# picjug.net
KiCad netlist of a schematic drawn in EAGLE
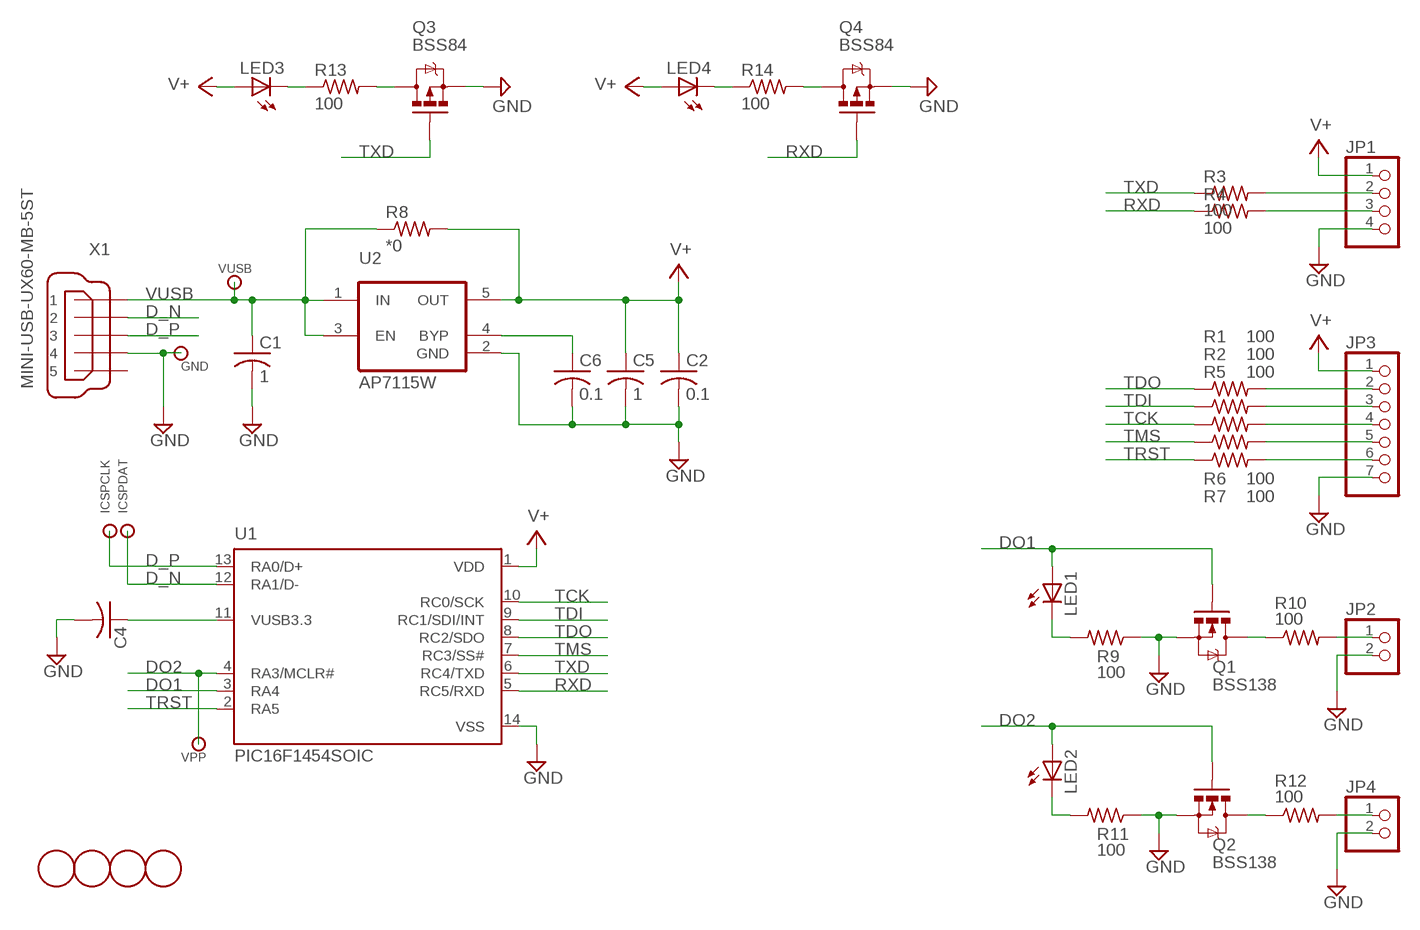
[diagram p0: schematic, sheet 1]

(export (version "E")
  (design (tool "Eeschema 10.0.6"))
  (components
    (comp (ref "C1")
      (value "1")
      (footprint "eagle-import:C0805")
      (libsource (lib "eagle-import") (part "C-USC0805"))
    )
    (comp (ref "C2")
      (value "0.1")
      (footprint "eagle-import:C0805")
      (libsource (lib "eagle-import") (part "C-USC0805"))
    )
    (comp (ref "C4")
      (value "C-USC0805")
      (footprint "eagle-import:C0805")
      (libsource (lib "eagle-import") (part "C-USC0805"))
    )
    (comp (ref "C5")
      (value "1")
      (footprint "eagle-import:C0805")
      (libsource (lib "eagle-import") (part "C-USC0805"))
    )
    (comp (ref "C6")
      (value "0.1")
      (footprint "eagle-import:C0805")
      (libsource (lib "eagle-import") (part "C-USC0805"))
    )
    (comp (ref "GND")
      (value "TESTPOINTMILLMAX_0900_SMALL")
      (footprint "eagle-import:0900-SERIES-SM")
      (libsource (lib "eagle-import") (part "TESTPOINTMILLMAX_0900_SMALL"))
    )
    (comp (ref "ICSPCLK")
      (value "TESTPOINTMILLMAX_0900_SMALL")
      (footprint "eagle-import:0900-SERIES-SM")
      (libsource (lib "eagle-import") (part "TESTPOINTMILLMAX_0900_SMALL"))
    )
    (comp (ref "ICSPDAT")
      (value "TESTPOINTMILLMAX_0900_SMALL")
      (footprint "eagle-import:0900-SERIES-SM")
      (libsource (lib "eagle-import") (part "TESTPOINTMILLMAX_0900_SMALL"))
    )
    (comp (ref "JP1")
      (value "PINHD-1X4")
      (footprint "eagle-import:1X04")
      (libsource (lib "eagle-import") (part "PINHD-1X4"))
    )
    (comp (ref "JP2")
      (value "PINHD-1X2")
      (footprint "eagle-import:1X02")
      (libsource (lib "eagle-import") (part "PINHD-1X2"))
    )
    (comp (ref "JP3")
      (value "PINHD-1X7")
      (footprint "eagle-import:1X07")
      (libsource (lib "eagle-import") (part "PINHD-1X7"))
    )
    (comp (ref "JP4")
      (value "PINHD-1X2")
      (footprint "eagle-import:1X02")
      (libsource (lib "eagle-import") (part "PINHD-1X2"))
    )
    (comp (ref "LED1")
      (value "LEDCHIP-LED0805")
      (footprint "eagle-import:CHIP-LED0805")
      (libsource (lib "eagle-import") (part "LEDCHIP-LED0805"))
    )
    (comp (ref "LED2")
      (value "LEDCHIP-LED0805")
      (footprint "eagle-import:CHIP-LED0805")
      (libsource (lib "eagle-import") (part "LEDCHIP-LED0805"))
    )
    (comp (ref "LED3")
      (value "LEDCHIP-LED0805")
      (footprint "eagle-import:CHIP-LED0805")
      (libsource (lib "eagle-import") (part "LEDCHIP-LED0805"))
    )
    (comp (ref "LED4")
      (value "LEDCHIP-LED0805")
      (footprint "eagle-import:CHIP-LED0805")
      (libsource (lib "eagle-import") (part "LEDCHIP-LED0805"))
    )
    (comp (ref "Q1")
      (value "BSS138")
      (footprint "eagle-import:SOT23-3")
      (libsource (lib "eagle-import") (part "MOSFET-NCHANNELSMD"))
    )
    (comp (ref "Q2")
      (value "BSS138")
      (footprint "eagle-import:SOT23-3")
      (libsource (lib "eagle-import") (part "MOSFET-NCHANNELSMD"))
    )
    (comp (ref "Q3")
      (value "BSS84")
      (footprint "eagle-import:SOT23")
      (libsource (lib "eagle-import") (part "MOSFET-PCHANNELSOT23"))
    )
    (comp (ref "Q4")
      (value "BSS84")
      (footprint "eagle-import:SOT23")
      (libsource (lib "eagle-import") (part "MOSFET-PCHANNELSOT23"))
    )
    (comp (ref "R1")
      (value "100")
      (footprint "eagle-import:R0805")
      (libsource (lib "eagle-import") (part "R-US_R0805"))
    )
    (comp (ref "R2")
      (value "100")
      (footprint "eagle-import:R0805")
      (libsource (lib "eagle-import") (part "R-US_R0805"))
    )
    (comp (ref "R3")
      (value "100")
      (footprint "eagle-import:R0805")
      (libsource (lib "eagle-import") (part "R-US_R0805"))
    )
    (comp (ref "R4")
      (value "100")
      (footprint "eagle-import:R0805")
      (libsource (lib "eagle-import") (part "R-US_R0805"))
    )
    (comp (ref "R5")
      (value "100")
      (footprint "eagle-import:R0805")
      (libsource (lib "eagle-import") (part "R-US_R0805"))
    )
    (comp (ref "R6")
      (value "100")
      (footprint "eagle-import:R0805")
      (libsource (lib "eagle-import") (part "R-US_R0805"))
    )
    (comp (ref "R7")
      (value "100")
      (footprint "eagle-import:R0805")
      (libsource (lib "eagle-import") (part "R-US_R0805"))
    )
    (comp (ref "R8")
      (value "*0")
      (footprint "eagle-import:R0805")
      (libsource (lib "eagle-import") (part "R-US_R0805"))
    )
    (comp (ref "R9")
      (value "100")
      (footprint "eagle-import:R0805")
      (libsource (lib "eagle-import") (part "R-US_R0805"))
    )
    (comp (ref "R10")
      (value "100")
      (footprint "eagle-import:R0805")
      (libsource (lib "eagle-import") (part "R-US_R0805"))
    )
    (comp (ref "R11")
      (value "100")
      (footprint "eagle-import:R0805")
      (libsource (lib "eagle-import") (part "R-US_R0805"))
    )
    (comp (ref "R12")
      (value "100")
      (footprint "eagle-import:R0805")
      (libsource (lib "eagle-import") (part "R-US_R0805"))
    )
    (comp (ref "R13")
      (value "100")
      (footprint "eagle-import:R0805")
      (libsource (lib "eagle-import") (part "R-US_R0805"))
    )
    (comp (ref "R14")
      (value "100")
      (footprint "eagle-import:R0805")
      (libsource (lib "eagle-import") (part "R-US_R0805"))
    )
    (comp (ref "U$1")
      (value "MOUNTING_HOLENO_4")
      (footprint "eagle-import:HOLE_MTG_NO4")
      (libsource (lib "eagle-import") (part "MOUNTING_HOLENO_4"))
    )
    (comp (ref "U$2")
      (value "MOUNTING_HOLENO_4")
      (footprint "eagle-import:HOLE_MTG_NO4")
      (libsource (lib "eagle-import") (part "MOUNTING_HOLENO_4"))
    )
    (comp (ref "U$3")
      (value "MOUNTING_HOLENO_4")
      (footprint "eagle-import:HOLE_MTG_NO4")
      (libsource (lib "eagle-import") (part "MOUNTING_HOLENO_4"))
    )
    (comp (ref "U$4")
      (value "MOUNTING_HOLENO_4")
      (footprint "eagle-import:HOLE_MTG_NO4")
      (libsource (lib "eagle-import") (part "MOUNTING_HOLENO_4"))
    )
    (comp (ref "U1")
      (value "PIC16F1454SOIC")
      (footprint "eagle-import:SOIC14")
      (libsource (lib "eagle-import") (part "PIC16F1454SOIC"))
    )
    (comp (ref "U2")
      (value "AP7115W")
      (footprint "eagle-import:SOT25")
      (libsource (lib "eagle-import") (part "AP7115W"))
    )
    (comp (ref "VPP")
      (value "TESTPOINTMILLMAX_0900_SMALL")
      (footprint "eagle-import:0900-SERIES-SM")
      (libsource (lib "eagle-import") (part "TESTPOINTMILLMAX_0900_SMALL"))
    )
    (comp (ref "VUSB")
      (value "TESTPOINTMILLMAX_0900_SMALL")
      (footprint "eagle-import:0900-SERIES-SM")
      (libsource (lib "eagle-import") (part "TESTPOINTMILLMAX_0900_SMALL"))
    )
    (comp (ref "X1")
      (value "MINI-USB-UX60-MB-5ST")
      (footprint "eagle-import:UX60-MB-5ST")
      (libsource (lib "eagle-import") (part "MINI-USB-UX60-MB-5ST"))
    )
  )
  (nets
    (net (code "1") (name "/DO1") (class "Default")
      (node (ref "LED1") (pin "A") (pinfunction "A_A") (pintype "passive"))
      (node (ref "Q1") (pin "1") (pinfunction "G_1") (pintype "passive"))
      (node (ref "U1") (pin "3") (pinfunction "RA4_3") (pintype "bidirectional"))
    )
    (net (code "2") (name "/DO2") (class "Default")
      (node (ref "LED2") (pin "A") (pinfunction "A_A") (pintype "passive"))
      (node (ref "Q2") (pin "1") (pinfunction "G_1") (pintype "passive"))
      (node (ref "U1") (pin "4") (pinfunction "RA3/MCLR#_4") (pintype "bidirectional"))
      (node (ref "VPP") (pin "P$1") (pinfunction "1_P$1") (pintype "passive"))
    )
    (net (code "3") (name "/D_N") (class "Default")
      (node (ref "ICSPDAT") (pin "P$1") (pinfunction "1_P$1") (pintype "passive"))
      (node (ref "U1") (pin "12") (pinfunction "RA1/D-_12") (pintype "bidirectional"))
      (node (ref "X1") (pin "2") (pinfunction "2_2") (pintype "input"))
    )
    (net (code "4") (name "/D_P") (class "Default")
      (node (ref "ICSPCLK") (pin "P$1") (pinfunction "1_P$1") (pintype "passive"))
      (node (ref "U1") (pin "13") (pinfunction "RA0/D+_13") (pintype "bidirectional"))
      (node (ref "X1") (pin "3") (pinfunction "3_3") (pintype "input"))
    )
    (net (code "5") (name "/RXD") (class "Default")
      (node (ref "Q4") (pin "1") (pinfunction "G_1") (pintype "passive"))
      (node (ref "R4") (pin "1") (pinfunction "1_1") (pintype "passive"))
      (node (ref "U1") (pin "5") (pinfunction "RC5/RXD_5") (pintype "bidirectional"))
    )
    (net (code "6") (name "/TCK") (class "Default")
      (node (ref "R5") (pin "1") (pinfunction "1_1") (pintype "passive"))
      (node (ref "U1") (pin "10") (pinfunction "RC0/SCK_10") (pintype "bidirectional"))
    )
    (net (code "7") (name "/TDI") (class "Default")
      (node (ref "R2") (pin "1") (pinfunction "1_1") (pintype "passive"))
      (node (ref "U1") (pin "9") (pinfunction "RC1/SDI/INT_9") (pintype "bidirectional"))
    )
    (net (code "8") (name "/TDO") (class "Default")
      (node (ref "R1") (pin "1") (pinfunction "1_1") (pintype "passive"))
      (node (ref "U1") (pin "8") (pinfunction "RC2/SDO_8") (pintype "bidirectional"))
    )
    (net (code "9") (name "/TMS") (class "Default")
      (node (ref "R6") (pin "1") (pinfunction "1_1") (pintype "passive"))
      (node (ref "U1") (pin "7") (pinfunction "RC3/SS#_7") (pintype "bidirectional"))
    )
    (net (code "10") (name "/TRST") (class "Default")
      (node (ref "R7") (pin "1") (pinfunction "1_1") (pintype "passive"))
      (node (ref "U1") (pin "2") (pinfunction "RA5_2") (pintype "bidirectional"))
    )
    (net (code "11") (name "/TXD") (class "Default")
      (node (ref "Q3") (pin "1") (pinfunction "G_1") (pintype "passive"))
      (node (ref "R3") (pin "1") (pinfunction "1_1") (pintype "passive"))
      (node (ref "U1") (pin "6") (pinfunction "RC4/TXD_6") (pintype "bidirectional"))
    )
    (net (code "12") (name "/VUSB") (class "Default")
      (node (ref "C1") (pin "1") (pinfunction "1_1") (pintype "passive"))
      (node (ref "R8") (pin "1") (pinfunction "1_1") (pintype "passive"))
      (node (ref "U2") (pin "1") (pinfunction "IN_1") (pintype "power_in"))
      (node (ref "U2") (pin "3") (pinfunction "EN_3") (pintype "bidirectional"))
      (node (ref "VUSB") (pin "P$1") (pinfunction "1_P$1") (pintype "passive"))
      (node (ref "X1") (pin "1") (pinfunction "1_1") (pintype "input"))
    )
    (net (code "13") (name "GND") (class "Default")
      (node (ref "C1") (pin "2") (pinfunction "2_2") (pintype "passive"))
      (node (ref "C2") (pin "2") (pinfunction "2_2") (pintype "passive"))
      (node (ref "C4") (pin "2") (pinfunction "2_2") (pintype "passive"))
      (node (ref "C5") (pin "2") (pinfunction "2_2") (pintype "passive"))
      (node (ref "C6") (pin "2") (pinfunction "2_2") (pintype "passive"))
      (node (ref "GND") (pin "P$1") (pinfunction "1_P$1") (pintype "passive"))
      (node (ref "JP1") (pin "4") (pinfunction "4_4") (pintype "passive"))
      (node (ref "JP2") (pin "2") (pinfunction "2_2") (pintype "passive"))
      (node (ref "JP3") (pin "7") (pinfunction "7_7") (pintype "passive"))
      (node (ref "JP4") (pin "2") (pinfunction "2_2") (pintype "passive"))
      (node (ref "Q1") (pin "2") (pinfunction "S_2") (pintype "passive"))
      (node (ref "Q2") (pin "2") (pinfunction "S_2") (pintype "passive"))
      (node (ref "Q3") (pin "2") (pinfunction "S_2") (pintype "passive"))
      (node (ref "Q4") (pin "2") (pinfunction "S_2") (pintype "passive"))
      (node (ref "R11") (pin "1") (pinfunction "1_1") (pintype "passive"))
      (node (ref "R9") (pin "1") (pinfunction "1_1") (pintype "passive"))
      (node (ref "U1") (pin "14") (pinfunction "VSS_14") (pintype "power_in"))
      (node (ref "U2") (pin "2") (pinfunction "GND_2") (pintype "power_in"))
      (node (ref "X1") (pin "4") (pinfunction "4_4") (pintype "input"))
    )
    (net (code "14") (name "Net-(JP1-Pad2)") (class "Default")
      (node (ref "JP1") (pin "2") (pinfunction "2_2") (pintype "passive"))
      (node (ref "R3") (pin "2") (pinfunction "2_2") (pintype "passive"))
    )
    (net (code "15") (name "Net-(JP1-Pad3)") (class "Default")
      (node (ref "JP1") (pin "3") (pinfunction "3_3") (pintype "passive"))
      (node (ref "R4") (pin "2") (pinfunction "2_2") (pintype "passive"))
    )
    (net (code "16") (name "Net-(JP2-Pad1)") (class "Default")
      (node (ref "JP2") (pin "1") (pinfunction "1_1") (pintype "passive"))
      (node (ref "R10") (pin "2") (pinfunction "2_2") (pintype "passive"))
    )
    (net (code "17") (name "Net-(JP3-Pad2)") (class "Default")
      (node (ref "JP3") (pin "2") (pinfunction "2_2") (pintype "passive"))
      (node (ref "R1") (pin "2") (pinfunction "2_2") (pintype "passive"))
    )
    (net (code "18") (name "Net-(JP3-Pad3)") (class "Default")
      (node (ref "JP3") (pin "3") (pinfunction "3_3") (pintype "passive"))
      (node (ref "R2") (pin "2") (pinfunction "2_2") (pintype "passive"))
    )
    (net (code "19") (name "Net-(JP3-Pad4)") (class "Default")
      (node (ref "JP3") (pin "4") (pinfunction "4_4") (pintype "passive"))
      (node (ref "R5") (pin "2") (pinfunction "2_2") (pintype "passive"))
    )
    (net (code "20") (name "Net-(JP3-Pad5)") (class "Default")
      (node (ref "JP3") (pin "5") (pinfunction "5_5") (pintype "passive"))
      (node (ref "R6") (pin "2") (pinfunction "2_2") (pintype "passive"))
    )
    (net (code "21") (name "Net-(JP3-Pad6)") (class "Default")
      (node (ref "JP3") (pin "6") (pinfunction "6_6") (pintype "passive"))
      (node (ref "R7") (pin "2") (pinfunction "2_2") (pintype "passive"))
    )
    (net (code "22") (name "Net-(JP4-Pad1)") (class "Default")
      (node (ref "JP4") (pin "1") (pinfunction "1_1") (pintype "passive"))
      (node (ref "R12") (pin "2") (pinfunction "2_2") (pintype "passive"))
    )
    (net (code "23") (name "Net-(LED1-PadC)") (class "Default")
      (node (ref "LED1") (pin "C") (pinfunction "C_C") (pintype "passive"))
      (node (ref "R9") (pin "2") (pinfunction "2_2") (pintype "passive"))
    )
    (net (code "24") (name "Net-(LED2-PadC)") (class "Default")
      (node (ref "LED2") (pin "C") (pinfunction "C_C") (pintype "passive"))
      (node (ref "R11") (pin "2") (pinfunction "2_2") (pintype "passive"))
    )
    (net (code "25") (name "Net-(LED3-PadC)") (class "Default")
      (node (ref "LED3") (pin "C") (pinfunction "C_C") (pintype "passive"))
      (node (ref "R13") (pin "1") (pinfunction "1_1") (pintype "passive"))
    )
    (net (code "26") (name "Net-(LED4-PadC)") (class "Default")
      (node (ref "LED4") (pin "C") (pinfunction "C_C") (pintype "passive"))
      (node (ref "R14") (pin "1") (pinfunction "1_1") (pintype "passive"))
    )
    (net (code "27") (name "Net-(Q1-D)") (class "Default")
      (node (ref "Q1") (pin "3") (pinfunction "D_3") (pintype "passive"))
      (node (ref "R10") (pin "1") (pinfunction "1_1") (pintype "passive"))
    )
    (net (code "28") (name "Net-(Q2-D)") (class "Default")
      (node (ref "Q2") (pin "3") (pinfunction "D_3") (pintype "passive"))
      (node (ref "R12") (pin "1") (pinfunction "1_1") (pintype "passive"))
    )
    (net (code "29") (name "Net-(Q3-D)") (class "Default")
      (node (ref "Q3") (pin "3") (pinfunction "D_3") (pintype "passive"))
      (node (ref "R13") (pin "2") (pinfunction "2_2") (pintype "passive"))
    )
    (net (code "30") (name "Net-(Q4-D)") (class "Default")
      (node (ref "Q4") (pin "3") (pinfunction "D_3") (pintype "passive"))
      (node (ref "R14") (pin "2") (pinfunction "2_2") (pintype "passive"))
    )
    (net (code "31") (name "Net-(U1-VUSB3.3)") (class "Default")
      (node (ref "C4") (pin "1") (pinfunction "1_1") (pintype "passive"))
      (node (ref "U1") (pin "11") (pinfunction "VUSB3.3_11") (pintype "power_in"))
    )
    (net (code "32") (name "Net-(U2-BYP)") (class "Default")
      (node (ref "C6") (pin "1") (pinfunction "1_1") (pintype "passive"))
      (node (ref "U2") (pin "4") (pinfunction "BYP_4") (pintype "passive"))
    )
    (net (code "33") (name "V+") (class "Default")
      (node (ref "C2") (pin "1") (pinfunction "1_1") (pintype "passive"))
      (node (ref "C5") (pin "1") (pinfunction "1_1") (pintype "passive"))
      (node (ref "JP1") (pin "1") (pinfunction "1_1") (pintype "passive"))
      (node (ref "JP3") (pin "1") (pinfunction "1_1") (pintype "passive"))
      (node (ref "LED3") (pin "A") (pinfunction "A_A") (pintype "passive"))
      (node (ref "LED4") (pin "A") (pinfunction "A_A") (pintype "passive"))
      (node (ref "R8") (pin "2") (pinfunction "2_2") (pintype "passive"))
      (node (ref "U1") (pin "1") (pinfunction "VDD_1") (pintype "power_in"))
      (node (ref "U2") (pin "5") (pinfunction "OUT_5") (pintype "power_in"))
    )
    (net (code "34") (name "unconnected-(X1-Pad5)") (class "Default")
      (node (ref "X1") (pin "5") (pinfunction "5_5") (pintype "input"))
    )
  )
)
